# ESC_dev_board.net
KiCad netlist of a schematic drawn in Altium Designer
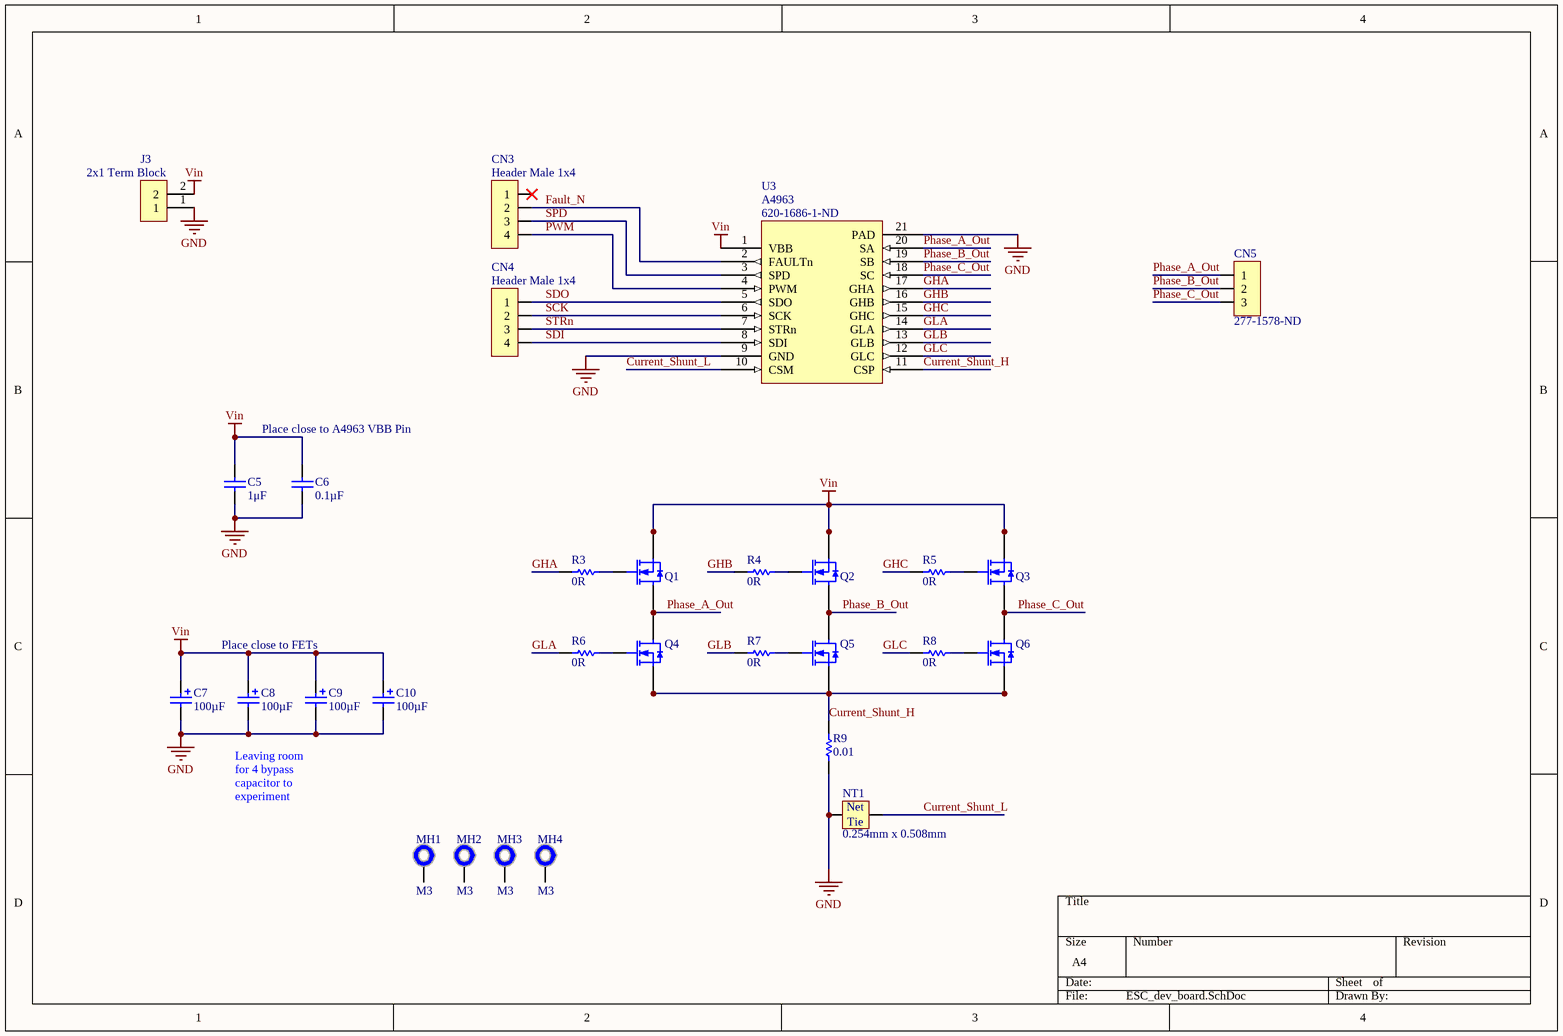
[diagram p0: ESC_dev_board.SchDoc]

(export (version "E")
  (design (tool "Eeschema 10.0.6"))
  (components
    (comp (ref "C5")
      (value "1μF")
      (footprint "CAPC1608N(0603\")")
      (description "Capacitor, Ceramic, 50V, +/- 10%, 0603 SMD, X5R")
      (fields (field (name "CREATED BY") "Lyden Smith"))
      (libsource (lib "AUVic_Integrated_Library_Capacitors") (part "1uF 50V 0603 SMD, Ceramic"))
    )
    (comp (ref "C6")
      (value "0.1uF, 50V, 10%, X7R, 0603")
      (footprint "CAPC1608N(0603\")")
      (description "0.1µF ±20% Ceramic Capacitor X7R 0603 (1608 Metric)")
      (fields (field (name "CAPACITANCE") "0.1µF") (field (name "CREATED BY") "Poorna Chander Kalidas"))
      (libsource (lib "AUVic_Integrated_Library_Capacitors") (part "0.1uF, 50V, 10%, X7R, 0603"))
    )
    (comp (ref "C7")
      (value "100µF")
      (footprint "Radial_CAN_6.6mm")
      (description "100µF 35V Aluminum Polymer Capacitor Radial, Can - SMD 30mOhm 2000 Hrs @ 105°C")
      (fields (field (name "CREATED BY") "Poorna Chander Kalidas"))
      (libsource (lib "AUVic_Integrated_Library_Capacitors") (part "100uF, 35V, 20%, 30mOhm, Alum, SMD"))
    )
    (comp (ref "C8")
      (value "100µF")
      (footprint "Radial_CAN_6.6mm")
      (description "100µF 35V Aluminum Polymer Capacitor Radial, Can - SMD 30mOhm 2000 Hrs @ 105°C")
      (fields (field (name "CREATED BY") "Poorna Chander Kalidas"))
      (libsource (lib "AUVic_Integrated_Library_Capacitors") (part "100uF, 35V, 20%, 30mOhm, Alum, SMD"))
    )
    (comp (ref "C9")
      (value "100µF")
      (footprint "Radial_CAN_6.6mm")
      (description "100µF 35V Aluminum Polymer Capacitor Radial, Can - SMD 30mOhm 2000 Hrs @ 105°C")
      (fields (field (name "CREATED BY") "Poorna Chander Kalidas"))
      (libsource (lib "AUVic_Integrated_Library_Capacitors") (part "100uF, 35V, 20%, 30mOhm, Alum, SMD"))
    )
    (comp (ref "C10")
      (value "100µF")
      (footprint "Radial_CAN_6.6mm")
      (description "100µF 35V Aluminum Polymer Capacitor Radial, Can - SMD 30mOhm 2000 Hrs @ 105°C")
      (fields (field (name "CREATED BY") "Poorna Chander Kalidas"))
      (libsource (lib "AUVic_Integrated_Library_Capacitors") (part "100uF, 35V, 20%, 30mOhm, Alum, SMD"))
    )
    (comp (ref "CN3")
      (value "Header Male 1x4")
      (footprint "Header, Male, 1X4")
      (description "1x4, Pads Pitch: 0.1\" (2.54mm), Through hole")
      (libsource (lib "AUVic_Integrated_Library_Connectors") (part "Header, Male, 1x4"))
    )
    (comp (ref "CN4")
      (value "Header Male 1x4")
      (footprint "Header, Male, 1X4")
      (description "1x4, Pads Pitch: 0.1\" (2.54mm), Through hole")
      (libsource (lib "AUVic_Integrated_Library_Connectors") (part "Header, Male, 1x4"))
    )
    (comp (ref "CN5")
      (value "3x1, Terminal Block, Pitch: 5mm, Screw, THT")
      (footprint "3x1, Terminal Block, Pitch: 5mm, Screw, THT")
      (fields
        (field (name "SUPPLIER PART NUMBER 1") "277-1578-ND")
        (field (name "PUBLISHER") "AUVic, Ashwin Sira")
        (field (name "REVIEWED BY") "*")
      )
      (libsource (lib "AUVic_Integrated_Library_Connectors") (part "3x1, Terminal Block, Pitch{colon} 5mm, Screw, THT"))
    )
    (comp (ref "J3")
      (value "2x1 Term Block")
      (footprint "2X1 Terminal Blocks Phoenix Contact 5mm")
      (fields (field (name "MADE BY") "Andy Bates"))
      (libsource (lib "AUVic_Integrated_Library_Connectors") (part "2x1 Terminal Block, 20A, 12-20AWG"))
    )
    (comp (ref "MH1")
      (value "M3")
      (footprint "Clearance_M3_PLATED")
      (description "Mounting Hole, M3, Plated")
      (fields (field (name "CREATED BY") "Ashwin Sira") (field (name "PUBLISHER") "AUVic"))
      (libsource (lib "AUVic_Integrated_Library_Virtual_Components") (part "Mounting Hole, M3, Plated"))
    )
    (comp (ref "MH2")
      (value "M3")
      (footprint "Clearance_M3_PLATED")
      (description "Mounting Hole, M3, Plated")
      (fields (field (name "CREATED BY") "Ashwin Sira") (field (name "PUBLISHER") "AUVic"))
      (libsource (lib "AUVic_Integrated_Library_Virtual_Components") (part "Mounting Hole, M3, Plated"))
    )
    (comp (ref "MH3")
      (value "M3")
      (footprint "Clearance_M3_PLATED")
      (description "Mounting Hole, M3, Plated")
      (fields (field (name "CREATED BY") "Ashwin Sira") (field (name "PUBLISHER") "AUVic"))
      (libsource (lib "AUVic_Integrated_Library_Virtual_Components") (part "Mounting Hole, M3, Plated"))
    )
    (comp (ref "MH4")
      (value "M3")
      (footprint "Clearance_M3_PLATED")
      (description "Mounting Hole, M3, Plated")
      (fields (field (name "CREATED BY") "Ashwin Sira") (field (name "PUBLISHER") "AUVic"))
      (libsource (lib "AUVic_Integrated_Library_Virtual_Components") (part "Mounting Hole, M3, Plated"))
    )
    (comp (ref "NT1")
      (value "0.254mm x 0.508mm")
      (footprint "NETTIE_20mil")
      (description "Net Tie, 20mil by 20mil")
      (fields (field (name "CREATED BY") "Ashwin Sira") (field (name "PUBLISHER") "AUVic"))
      (libsource (lib "AUVic_Integrated_Library_Virtual_Components") (part "Net Tie, 20mil"))
    )
    (comp (ref "Q1")
      (value "SI7625DN-T1-GE3")
      (footprint "PowerPAK 1212-8")
      (description "P-Channel 30V 35A (Tc) 3.7W (Ta), 52W (Tc) Surface Mount PowerPAK® 1212-8")
      (fields (field (name "CREATED BY") "Poorna Chander Kalidas"))
      (libsource (lib "AUVic_Integrated_Library_Transistors") (part "SI7625DN-T1-GE3"))
    )
    (comp (ref "Q2")
      (value "SI7625DN-T1-GE3")
      (footprint "PowerPAK 1212-8")
      (description "P-Channel 30V 35A (Tc) 3.7W (Ta), 52W (Tc) Surface Mount PowerPAK® 1212-8")
      (fields (field (name "CREATED BY") "Poorna Chander Kalidas"))
      (libsource (lib "AUVic_Integrated_Library_Transistors") (part "SI7625DN-T1-GE3"))
    )
    (comp (ref "Q3")
      (value "SI7625DN-T1-GE3")
      (footprint "PowerPAK 1212-8")
      (description "P-Channel 30V 35A (Tc) 3.7W (Ta), 52W (Tc) Surface Mount PowerPAK® 1212-8")
      (fields (field (name "CREATED BY") "Poorna Chander Kalidas"))
      (libsource (lib "AUVic_Integrated_Library_Transistors") (part "SI7625DN-T1-GE3"))
    )
    (comp (ref "Q4")
      (value "SIS476DN-T1-GE3")
      (footprint "PowerPAK 1212-8")
      (description "N-Channel 30V 40A (Tc) 3.7W (Ta), 52W (Tc) Surface Mount PowerPAK® 1212-8")
      (fields (field (name "CREATED BY") "Poorna Chander Kalidas"))
      (libsource (lib "AUVic_Integrated_Library_Transistors") (part "SIS476DN-T1-GE3"))
    )
    (comp (ref "Q5")
      (value "SIS476DN-T1-GE3")
      (footprint "PowerPAK 1212-8")
      (description "N-Channel 30V 40A (Tc) 3.7W (Ta), 52W (Tc) Surface Mount PowerPAK® 1212-8")
      (fields (field (name "CREATED BY") "Poorna Chander Kalidas"))
      (libsource (lib "AUVic_Integrated_Library_Transistors") (part "SIS476DN-T1-GE3"))
    )
    (comp (ref "Q6")
      (value "SIS476DN-T1-GE3")
      (footprint "PowerPAK 1212-8")
      (description "N-Channel 30V 40A (Tc) 3.7W (Ta), 52W (Tc) Surface Mount PowerPAK® 1212-8")
      (fields (field (name "CREATED BY") "Poorna Chander Kalidas"))
      (libsource (lib "AUVic_Integrated_Library_Transistors") (part "SIS476DN-T1-GE3"))
    )
    (comp (ref "R3")
      (value "0R")
      (footprint "RESC1608N(0603\")")
      (description "0R, 1%, 1/10W, 0603 SMD")
      (fields (field (name "MADE BY") "Ashwin Sira"))
      (libsource (lib "AUVic_Integrated_Library_Resistors") (part "0R, 1%, 1/10W, 0603 SMD"))
    )
    (comp (ref "R4")
      (value "0R")
      (footprint "RESC1608N(0603\")")
      (description "0R, 1%, 1/10W, 0603 SMD")
      (fields (field (name "MADE BY") "Ashwin Sira"))
      (libsource (lib "AUVic_Integrated_Library_Resistors") (part "0R, 1%, 1/10W, 0603 SMD"))
    )
    (comp (ref "R5")
      (value "0R")
      (footprint "RESC1608N(0603\")")
      (description "0R, 1%, 1/10W, 0603 SMD")
      (fields (field (name "MADE BY") "Ashwin Sira"))
      (libsource (lib "AUVic_Integrated_Library_Resistors") (part "0R, 1%, 1/10W, 0603 SMD"))
    )
    (comp (ref "R6")
      (value "0R")
      (footprint "RESC1608N(0603\")")
      (description "0R, 1%, 1/10W, 0603 SMD")
      (fields (field (name "MADE BY") "Ashwin Sira"))
      (libsource (lib "AUVic_Integrated_Library_Resistors") (part "0R, 1%, 1/10W, 0603 SMD"))
    )
    (comp (ref "R7")
      (value "0R")
      (footprint "RESC1608N(0603\")")
      (description "0R, 1%, 1/10W, 0603 SMD")
      (fields (field (name "MADE BY") "Ashwin Sira"))
      (libsource (lib "AUVic_Integrated_Library_Resistors") (part "0R, 1%, 1/10W, 0603 SMD"))
    )
    (comp (ref "R8")
      (value "0R")
      (footprint "RESC1608N(0603\")")
      (description "0R, 1%, 1/10W, 0603 SMD")
      (fields (field (name "MADE BY") "Ashwin Sira"))
      (libsource (lib "AUVic_Integrated_Library_Resistors") (part "0R, 1%, 1/10W, 0603 SMD"))
    )
    (comp (ref "R9")
      (value "0.01")
      (footprint "RESC6332N(2512\")")
      (description "RES 0.01 OHM 1% 3W 2512")
      (fields (field (name "CREATED BY") "Poorna Chander Kalidas"))
      (libsource (lib "AUVic_Integrated_Library_Resistors") (part "0R01, 1%, 3W, 2512 SMD"))
    )
    (comp (ref "U3")
      (value "A4963")
      (footprint "TSOP65P640X120_HS-21M")
      (description "A4963, BLDC, 3 Phase, Sensorless")
      (fields
        (field (name "SUPPLIER PART NUMBER 1") "620-1686-1-ND")
        (field (name "CREATED BY") "Poorna Chander Kalidas")
      )
      (libsource (lib "AUVic_Integrated_Library_Motor_Controllers") (part "A4963, BLDC, 3Phase"))
    )
  )
  (nets
    (net (code "1") (name "/Current_Shunt_H") (class "Default")
      (node (ref "Q4") (pin "1") (pinfunction "Source_1") (pintype "passive"))
      (node (ref "Q4") (pin "2") (pinfunction "Source_2") (pintype "passive"))
      (node (ref "Q4") (pin "3") (pinfunction "Source_3") (pintype "passive"))
      (node (ref "Q5") (pin "1") (pinfunction "Source_1") (pintype "passive"))
      (node (ref "Q5") (pin "2") (pinfunction "Source_2") (pintype "passive"))
      (node (ref "Q5") (pin "3") (pinfunction "Source_3") (pintype "passive"))
      (node (ref "Q6") (pin "1") (pinfunction "Source_1") (pintype "passive"))
      (node (ref "Q6") (pin "2") (pinfunction "Source_2") (pintype "passive"))
      (node (ref "Q6") (pin "3") (pinfunction "Source_3") (pintype "passive"))
      (node (ref "R9") (pin "2") (pinfunction "2_2") (pintype "passive"))
      (node (ref "U3") (pin "11") (pinfunction "CSP_11") (pintype "input"))
    )
    (net (code "2") (name "/Current_Shunt_L") (class "Default")
      (node (ref "NT1") (pin "2") (pinfunction "2_2") (pintype "passive"))
      (node (ref "U3") (pin "10") (pinfunction "CSM_10") (pintype "input"))
    )
    (net (code "3") (name "/Fault_N") (class "Default")
      (node (ref "CN3") (pin "2") (pinfunction "2_2") (pintype "passive"))
      (node (ref "U3") (pin "2") (pinfunction "FAULTn_2") (pintype "output"))
    )
    (net (code "4") (name "/GHA") (class "Default")
      (node (ref "R3") (pin "1") (pinfunction "1_1") (pintype "passive"))
      (node (ref "U3") (pin "17") (pinfunction "GHA_17") (pintype "output"))
    )
    (net (code "5") (name "/GHB") (class "Default")
      (node (ref "R4") (pin "1") (pinfunction "1_1") (pintype "passive"))
      (node (ref "U3") (pin "16") (pinfunction "GHB_16") (pintype "output"))
    )
    (net (code "6") (name "/GHC") (class "Default")
      (node (ref "R5") (pin "1") (pinfunction "1_1") (pintype "passive"))
      (node (ref "U3") (pin "15") (pinfunction "GHC_15") (pintype "output"))
    )
    (net (code "7") (name "/GLA") (class "Default")
      (node (ref "R6") (pin "1") (pinfunction "1_1") (pintype "passive"))
      (node (ref "U3") (pin "14") (pinfunction "GLA_14") (pintype "output"))
    )
    (net (code "8") (name "/GLB") (class "Default")
      (node (ref "R7") (pin "1") (pinfunction "1_1") (pintype "passive"))
      (node (ref "U3") (pin "13") (pinfunction "GLB_13") (pintype "output"))
    )
    (net (code "9") (name "/GLC") (class "Default")
      (node (ref "R8") (pin "1") (pinfunction "1_1") (pintype "passive"))
      (node (ref "U3") (pin "12") (pinfunction "GLC_12") (pintype "output"))
    )
    (net (code "10") (name "/PWM") (class "Default")
      (node (ref "CN3") (pin "4") (pinfunction "4_4") (pintype "passive"))
      (node (ref "U3") (pin "4") (pinfunction "PWM_4") (pintype "input"))
    )
    (net (code "11") (name "/Phase_A_Out") (class "Default")
      (node (ref "CN5") (pin "1") (pinfunction "1_1") (pintype "passive"))
      (node (ref "Q1") (pin "5") (pinfunction "Drain_5") (pintype "passive"))
      (node (ref "Q1") (pin "6") (pinfunction "Drain_6") (pintype "passive"))
      (node (ref "Q1") (pin "7") (pinfunction "Drain_7") (pintype "passive"))
      (node (ref "Q1") (pin "8") (pinfunction "Drain_8") (pintype "passive"))
      (node (ref "Q1") (pin "9") (pinfunction "Drain_9") (pintype "passive"))
      (node (ref "Q4") (pin "5") (pinfunction "Drain_5") (pintype "passive"))
      (node (ref "Q4") (pin "6") (pinfunction "Drain_6") (pintype "passive"))
      (node (ref "Q4") (pin "7") (pinfunction "Drain_7") (pintype "passive"))
      (node (ref "Q4") (pin "8") (pinfunction "Drain_8") (pintype "passive"))
      (node (ref "Q4") (pin "9") (pinfunction "Drain_9") (pintype "passive"))
      (node (ref "U3") (pin "20") (pinfunction "SA_20") (pintype "input"))
    )
    (net (code "12") (name "/Phase_B_Out") (class "Default")
      (node (ref "CN5") (pin "2") (pinfunction "2_2") (pintype "passive"))
      (node (ref "Q2") (pin "5") (pinfunction "Drain_5") (pintype "passive"))
      (node (ref "Q2") (pin "6") (pinfunction "Drain_6") (pintype "passive"))
      (node (ref "Q2") (pin "7") (pinfunction "Drain_7") (pintype "passive"))
      (node (ref "Q2") (pin "8") (pinfunction "Drain_8") (pintype "passive"))
      (node (ref "Q2") (pin "9") (pinfunction "Drain_9") (pintype "passive"))
      (node (ref "Q5") (pin "5") (pinfunction "Drain_5") (pintype "passive"))
      (node (ref "Q5") (pin "6") (pinfunction "Drain_6") (pintype "passive"))
      (node (ref "Q5") (pin "7") (pinfunction "Drain_7") (pintype "passive"))
      (node (ref "Q5") (pin "8") (pinfunction "Drain_8") (pintype "passive"))
      (node (ref "Q5") (pin "9") (pinfunction "Drain_9") (pintype "passive"))
      (node (ref "U3") (pin "19") (pinfunction "SB_19") (pintype "input"))
    )
    (net (code "13") (name "/Phase_C_Out") (class "Default")
      (node (ref "CN5") (pin "3") (pinfunction "3_3") (pintype "passive"))
      (node (ref "Q3") (pin "5") (pinfunction "Drain_5") (pintype "passive"))
      (node (ref "Q3") (pin "6") (pinfunction "Drain_6") (pintype "passive"))
      (node (ref "Q3") (pin "7") (pinfunction "Drain_7") (pintype "passive"))
      (node (ref "Q3") (pin "8") (pinfunction "Drain_8") (pintype "passive"))
      (node (ref "Q3") (pin "9") (pinfunction "Drain_9") (pintype "passive"))
      (node (ref "Q6") (pin "5") (pinfunction "Drain_5") (pintype "passive"))
      (node (ref "Q6") (pin "6") (pinfunction "Drain_6") (pintype "passive"))
      (node (ref "Q6") (pin "7") (pinfunction "Drain_7") (pintype "passive"))
      (node (ref "Q6") (pin "8") (pinfunction "Drain_8") (pintype "passive"))
      (node (ref "Q6") (pin "9") (pinfunction "Drain_9") (pintype "passive"))
      (node (ref "U3") (pin "18") (pinfunction "SC_18") (pintype "input"))
    )
    (net (code "14") (name "/SCK") (class "Default")
      (node (ref "CN4") (pin "2") (pinfunction "2_2") (pintype "passive"))
      (node (ref "U3") (pin "6") (pinfunction "SCK_6") (pintype "input"))
    )
    (net (code "15") (name "/SDI") (class "Default")
      (node (ref "CN4") (pin "4") (pinfunction "4_4") (pintype "passive"))
      (node (ref "U3") (pin "8") (pinfunction "SDI_8") (pintype "input"))
    )
    (net (code "16") (name "/SDO") (class "Default")
      (node (ref "CN4") (pin "1") (pinfunction "1_1") (pintype "passive"))
      (node (ref "U3") (pin "5") (pinfunction "SDO_5") (pintype "output"))
    )
    (net (code "17") (name "/SPD") (class "Default")
      (node (ref "CN3") (pin "3") (pinfunction "3_3") (pintype "passive"))
      (node (ref "U3") (pin "3") (pinfunction "SPD_3") (pintype "output"))
    )
    (net (code "18") (name "/STRn") (class "Default")
      (node (ref "CN4") (pin "3") (pinfunction "3_3") (pintype "passive"))
      (node (ref "U3") (pin "7") (pinfunction "STRn_7") (pintype "input"))
    )
    (net (code "19") (name "GND") (class "Default")
      (node (ref "C10") (pin "2") (pinfunction "Cathode_2") (pintype "passive"))
      (node (ref "C5") (pin "1") (pinfunction "Anode_1") (pintype "passive"))
      (node (ref "C6") (pin "1") (pinfunction "Anode_1") (pintype "passive"))
      (node (ref "C7") (pin "2") (pinfunction "Cathode_2") (pintype "passive"))
      (node (ref "C8") (pin "2") (pinfunction "Cathode_2") (pintype "passive"))
      (node (ref "C9") (pin "2") (pinfunction "Cathode_2") (pintype "passive"))
      (node (ref "J3") (pin "1") (pinfunction "1_1") (pintype "passive"))
      (node (ref "NT1") (pin "1") (pinfunction "1_1") (pintype "passive"))
      (node (ref "R9") (pin "1") (pinfunction "1_1") (pintype "passive"))
      (node (ref "U3") (pin "21") (pinfunction "PAD_21") (pintype "power_in"))
      (node (ref "U3") (pin "9") (pinfunction "GND_9") (pintype "power_in"))
    )
    (net (code "20") (name "Net-(Q1-Gate)") (class "Default")
      (node (ref "Q1") (pin "4") (pinfunction "Gate_4") (pintype "passive"))
      (node (ref "R3") (pin "2") (pinfunction "2_2") (pintype "passive"))
    )
    (net (code "21") (name "Net-(Q2-Gate)") (class "Default")
      (node (ref "Q2") (pin "4") (pinfunction "Gate_4") (pintype "passive"))
      (node (ref "R4") (pin "2") (pinfunction "2_2") (pintype "passive"))
    )
    (net (code "22") (name "Net-(Q3-Gate)") (class "Default")
      (node (ref "Q3") (pin "4") (pinfunction "Gate_4") (pintype "passive"))
      (node (ref "R5") (pin "2") (pinfunction "2_2") (pintype "passive"))
    )
    (net (code "23") (name "Net-(Q4-Gate)") (class "Default")
      (node (ref "Q4") (pin "4") (pinfunction "Gate_4") (pintype "passive"))
      (node (ref "R6") (pin "2") (pinfunction "2_2") (pintype "passive"))
    )
    (net (code "24") (name "Net-(Q5-Gate)") (class "Default")
      (node (ref "Q5") (pin "4") (pinfunction "Gate_4") (pintype "passive"))
      (node (ref "R7") (pin "2") (pinfunction "2_2") (pintype "passive"))
    )
    (net (code "25") (name "Net-(Q6-Gate)") (class "Default")
      (node (ref "Q6") (pin "4") (pinfunction "Gate_4") (pintype "passive"))
      (node (ref "R8") (pin "2") (pinfunction "2_2") (pintype "passive"))
    )
    (net (code "26") (name "Vin") (class "Default")
      (node (ref "C10") (pin "1") (pinfunction "Anode_1") (pintype "passive"))
      (node (ref "C5") (pin "2") (pinfunction "Cathode_2") (pintype "passive"))
      (node (ref "C6") (pin "2") (pinfunction "Cathode_2") (pintype "passive"))
      (node (ref "C7") (pin "1") (pinfunction "Anode_1") (pintype "passive"))
      (node (ref "C8") (pin "1") (pinfunction "Anode_1") (pintype "passive"))
      (node (ref "C9") (pin "1") (pinfunction "Anode_1") (pintype "passive"))
      (node (ref "J3") (pin "2") (pinfunction "2_2") (pintype "passive"))
      (node (ref "Q1") (pin "1") (pinfunction "Source_1") (pintype "passive"))
      (node (ref "Q1") (pin "2") (pinfunction "Source_2") (pintype "passive"))
      (node (ref "Q1") (pin "3") (pinfunction "Source_3") (pintype "passive"))
      (node (ref "Q2") (pin "1") (pinfunction "Source_1") (pintype "passive"))
      (node (ref "Q2") (pin "2") (pinfunction "Source_2") (pintype "passive"))
      (node (ref "Q2") (pin "3") (pinfunction "Source_3") (pintype "passive"))
      (node (ref "Q3") (pin "1") (pinfunction "Source_1") (pintype "passive"))
      (node (ref "Q3") (pin "2") (pinfunction "Source_2") (pintype "passive"))
      (node (ref "Q3") (pin "3") (pinfunction "Source_3") (pintype "passive"))
      (node (ref "U3") (pin "1") (pinfunction "VBB_1") (pintype "power_in"))
    )
    (net (code "27") (name "unconnected-(CN3-Pad1)") (class "Default")
      (node (ref "CN3") (pin "1") (pinfunction "1_1") (pintype "passive+no_connect"))
    )
    (net (code "28") (name "unconnected-(MH1-Pad1)") (class "Default")
      (node (ref "MH1") (pin "1") (pinfunction "1_1") (pintype "passive"))
    )
    (net (code "29") (name "unconnected-(MH2-Pad1)") (class "Default")
      (node (ref "MH2") (pin "1") (pinfunction "1_1") (pintype "passive"))
    )
    (net (code "30") (name "unconnected-(MH3-Pad1)") (class "Default")
      (node (ref "MH3") (pin "1") (pinfunction "1_1") (pintype "passive"))
    )
    (net (code "31") (name "unconnected-(MH4-Pad1)") (class "Default")
      (node (ref "MH4") (pin "1") (pinfunction "1_1") (pintype "passive"))
    )
  )
)
